# YMFC.net
KiCad netlist of a schematic drawn in EAGLE
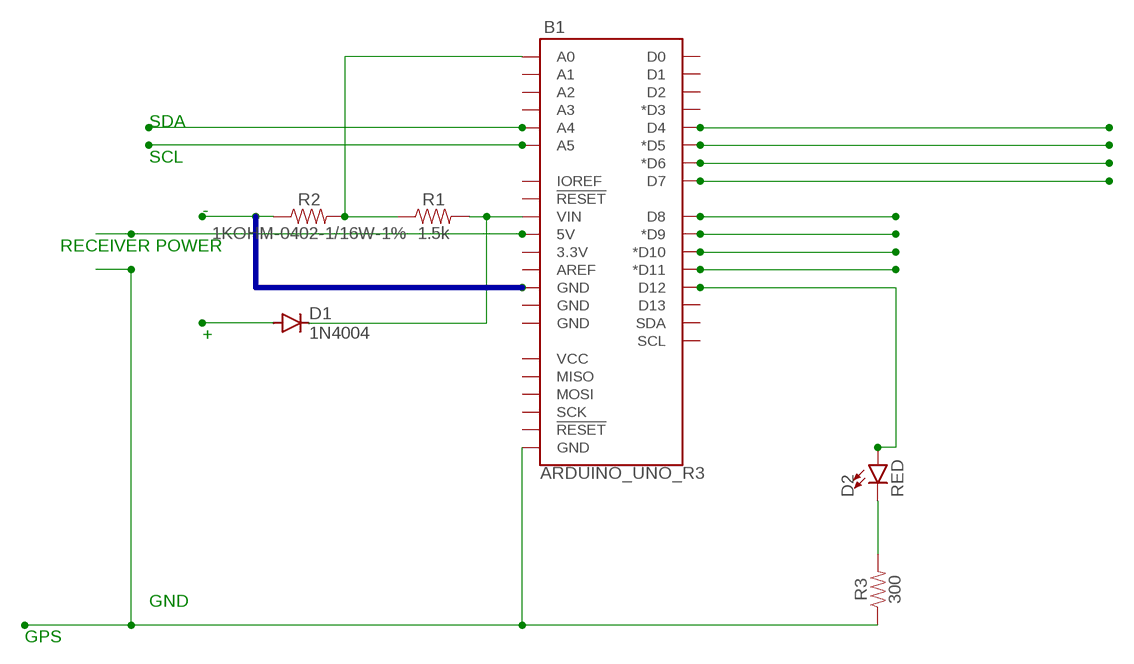
[diagram p0: schematic, sheet 1]

(export (version "E")
  (design (tool "Eeschema 10.0.6"))
  (components
    (comp (ref "B1")
      (value "ARDUINO_UNO_R3")
      (footprint "eagle-import:ARDUINO_R3")
      (libsource (lib "eagle-import") (part "ARDUINO_UNO_R3"))
    )
    (comp (ref "D1")
      (value "1N4004")
      (footprint "eagle-import:DO41-10")
      (libsource (lib "eagle-import") (part "1N4004"))
    )
    (comp (ref "D2")
      (value "RED")
      (footprint "eagle-import:LED-0603")
      (libsource (lib "eagle-import") (part "LED-RED0603"))
    )
    (comp (ref "R1")
      (value "1.5k")
      (footprint "eagle-import:0603")
      (libsource (lib "eagle-import") (part "1.5KOHM-0603-1/10W-1%"))
    )
    (comp (ref "R2")
      (value "1KOHM-0402-1/16W-1%")
      (footprint "eagle-import:0402")
      (libsource (lib "eagle-import") (part "1KOHM-0402-1/16W-1%"))
    )
    (comp (ref "R3")
      (value "300")
      (footprint "eagle-import:0603")
      (libsource (lib "eagle-import") (part "300OHM-0603-1/10W-1%"))
    )
  )
  (nets
    (net (code "1") (name "Net-(B1-GND-PadGND@1)") (class "Default")
      (node (ref "B1") (pin "GND@1") (pinfunction "GND_GND@1") (pintype "bidirectional"))
      (node (ref "R3") (pin "1") (pinfunction "1_1") (pintype "passive"))
    )
    (net (code "2") (name "Net-(B1-PadA0)") (class "Default")
      (node (ref "B1") (pin "A0") (pinfunction "A0_A0") (pintype "bidirectional"))
      (node (ref "R1") (pin "1") (pinfunction "1_1") (pintype "passive"))
      (node (ref "R2") (pin "2") (pinfunction "2_2") (pintype "passive"))
    )
    (net (code "3") (name "Net-(B1-PadD12)") (class "Default")
      (node (ref "B1") (pin "D12") (pinfunction "D12_D12") (pintype "bidirectional"))
      (node (ref "D2") (pin "A") (pinfunction "A_A") (pintype "passive"))
    )
    (net (code "4") (name "Net-(B1-PadVIN)") (class "Default")
      (node (ref "B1") (pin "VIN") (pinfunction "VIN_VIN") (pintype "bidirectional"))
      (node (ref "D1") (pin "C") (pinfunction "C_C") (pintype "passive"))
      (node (ref "R1") (pin "2") (pinfunction "2_2") (pintype "passive"))
    )
    (net (code "5") (name "Net-(D2-PadC)") (class "Default")
      (node (ref "D2") (pin "C") (pinfunction "C_C") (pintype "passive"))
      (node (ref "R3") (pin "2") (pinfunction "2_2") (pintype "passive"))
    )
    (net (code "6") (name "unconnected-(B1-*D3-PadD3)") (class "Default")
      (node (ref "B1") (pin "D3") (pinfunction "*D3_D3") (pintype "bidirectional"))
    )
    (net (code "7") (name "unconnected-(B1-*D5-PadD5)") (class "Default")
      (node (ref "B1") (pin "D5") (pinfunction "*D5_D5") (pintype "bidirectional"))
    )
    (net (code "8") (name "unconnected-(B1-*D6-PadD6)") (class "Default")
      (node (ref "B1") (pin "D6") (pinfunction "*D6_D6") (pintype "bidirectional"))
    )
    (net (code "9") (name "unconnected-(B1-*D9-PadD9)") (class "Default")
      (node (ref "B1") (pin "D9") (pinfunction "*D9_D9") (pintype "bidirectional"))
    )
    (net (code "10") (name "unconnected-(B1-*D10-PadD10)") (class "Default")
      (node (ref "B1") (pin "D10") (pinfunction "*D10_D10") (pintype "bidirectional"))
    )
    (net (code "11") (name "unconnected-(B1-*D11-PadD11)") (class "Default")
      (node (ref "B1") (pin "D11") (pinfunction "*D11_D11") (pintype "bidirectional"))
    )
    (net (code "12") (name "unconnected-(B1-GND-PadGND@2)") (class "Default")
      (node (ref "B1") (pin "GND@2") (pinfunction "GND_GND@2") (pintype "bidirectional"))
    )
    (net (code "13") (name "unconnected-(B1-GND-PadGND@3)") (class "Default")
      (node (ref "B1") (pin "GND@3") (pinfunction "GND_GND@3") (pintype "bidirectional"))
    )
    (net (code "14") (name "unconnected-(B1-GND-PadGND@4)") (class "Default")
      (node (ref "B1") (pin "GND@4") (pinfunction "GND_GND@4") (pintype "bidirectional"))
    )
    (net (code "15") (name "unconnected-(B1-Pad3.3V)") (class "Default")
      (node (ref "B1") (pin "3.3V") (pinfunction "3.3V_3.3V") (pintype "bidirectional"))
    )
    (net (code "16") (name "unconnected-(B1-Pad5V)") (class "Default")
      (node (ref "B1") (pin "5V") (pinfunction "5V_5V") (pintype "bidirectional"))
    )
    (net (code "17") (name "unconnected-(B1-PadA1)") (class "Default")
      (node (ref "B1") (pin "A1") (pinfunction "A1_A1") (pintype "bidirectional"))
    )
    (net (code "18") (name "unconnected-(B1-PadA2)") (class "Default")
      (node (ref "B1") (pin "A2") (pinfunction "A2_A2") (pintype "bidirectional"))
    )
    (net (code "19") (name "unconnected-(B1-PadA3)") (class "Default")
      (node (ref "B1") (pin "A3") (pinfunction "A3_A3") (pintype "bidirectional"))
    )
    (net (code "20") (name "unconnected-(B1-PadA4)") (class "Default")
      (node (ref "B1") (pin "A4") (pinfunction "A4_A4") (pintype "bidirectional"))
    )
    (net (code "21") (name "unconnected-(B1-PadA5)") (class "Default")
      (node (ref "B1") (pin "A5") (pinfunction "A5_A5") (pintype "bidirectional"))
    )
    (net (code "22") (name "unconnected-(B1-PadAREF)") (class "Default")
      (node (ref "B1") (pin "AREF") (pinfunction "AREF_AREF") (pintype "bidirectional"))
    )
    (net (code "23") (name "unconnected-(B1-PadD0)") (class "Default")
      (node (ref "B1") (pin "D0") (pinfunction "D0_D0") (pintype "bidirectional"))
    )
    (net (code "24") (name "unconnected-(B1-PadD1)") (class "Default")
      (node (ref "B1") (pin "D1") (pinfunction "D1_D1") (pintype "bidirectional"))
    )
    (net (code "25") (name "unconnected-(B1-PadD2)") (class "Default")
      (node (ref "B1") (pin "D2") (pinfunction "D2_D2") (pintype "bidirectional"))
    )
    (net (code "26") (name "unconnected-(B1-PadD4)") (class "Default")
      (node (ref "B1") (pin "D4") (pinfunction "D4_D4") (pintype "bidirectional"))
    )
    (net (code "27") (name "unconnected-(B1-PadD7)") (class "Default")
      (node (ref "B1") (pin "D7") (pinfunction "D7_D7") (pintype "bidirectional"))
    )
    (net (code "28") (name "unconnected-(B1-PadD8)") (class "Default")
      (node (ref "B1") (pin "D8") (pinfunction "D8_D8") (pintype "bidirectional"))
    )
    (net (code "29") (name "unconnected-(B1-PadD13)") (class "Default")
      (node (ref "B1") (pin "D13") (pinfunction "D13_D13") (pintype "bidirectional"))
    )
    (net (code "30") (name "unconnected-(B1-PadIOREF)") (class "Default")
      (node (ref "B1") (pin "IOREF") (pinfunction "IOREF_IOREF") (pintype "bidirectional"))
    )
    (net (code "31") (name "unconnected-(B1-PadMISO)") (class "Default")
      (node (ref "B1") (pin "MISO") (pinfunction "MISO_MISO") (pintype "bidirectional"))
    )
    (net (code "32") (name "unconnected-(B1-PadMOSI)") (class "Default")
      (node (ref "B1") (pin "MOSI") (pinfunction "MOSI_MOSI") (pintype "bidirectional"))
    )
    (net (code "33") (name "unconnected-(B1-PadSCK)") (class "Default")
      (node (ref "B1") (pin "SCK") (pinfunction "SCK_SCK") (pintype "bidirectional"))
    )
    (net (code "34") (name "unconnected-(B1-PadSCL)") (class "Default")
      (node (ref "B1") (pin "SCL") (pinfunction "SCL_SCL") (pintype "bidirectional"))
    )
    (net (code "35") (name "unconnected-(B1-PadSDA)") (class "Default")
      (node (ref "B1") (pin "SDA") (pinfunction "SDA_SDA") (pintype "bidirectional"))
    )
    (net (code "36") (name "unconnected-(B1-PadVCC)") (class "Default")
      (node (ref "B1") (pin "VCC") (pinfunction "VCC_VCC") (pintype "bidirectional"))
    )
    (net (code "37") (name "unconnected-(B1-~{RESET}-PadRESET@1)") (class "Default")
      (node (ref "B1") (pin "RESET@1") (pinfunction "~{RESET}_RESET@1") (pintype "bidirectional"))
    )
    (net (code "38") (name "unconnected-(B1-~{RESET}-PadRESET@2)") (class "Default")
      (node (ref "B1") (pin "RESET@2") (pinfunction "~{RESET}_RESET@2") (pintype "bidirectional"))
    )
    (net (code "39") (name "unconnected-(D1-PadA)") (class "Default")
      (node (ref "D1") (pin "A") (pinfunction "A_A") (pintype "passive"))
    )
    (net (code "40") (name "unconnected-(R2-Pad1)") (class "Default")
      (node (ref "R2") (pin "1") (pinfunction "1_1") (pintype "passive"))
    )
  )
)
